# ProgrammerBoardV1.net
KiCad netlist of a schematic drawn in EAGLE
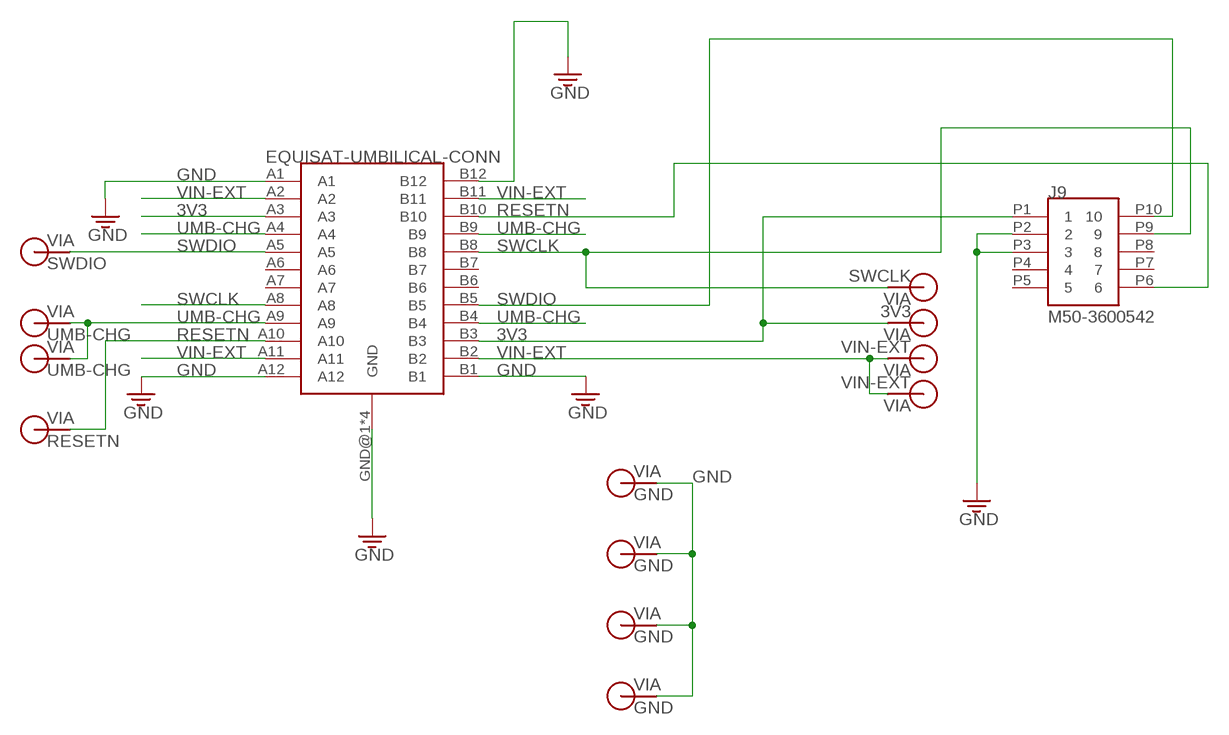
[diagram p0: schematic, sheet 1]

(export (version "E")
  (design (tool "Eeschema 10.0.6"))
  (components
    (comp (ref "J9")
      (value "M50-3600542")
      (footprint "eagle-import:10PINMALE")
      (libsource (lib "eagle-import") (part "10PINMALE"))
    )
    (comp (ref "U$1")
      (value "EQUISAT-UMBILICAL-CONN")
      (footprint "eagle-import:USB-C-RCPT-SMT")
      (libsource (lib "eagle-import") (part "EQUISAT-UMBILICAL-CONN"))
    )
    (comp (ref "V1")
      (value "GND")
      (footprint "eagle-import:VIA-60MIL")
      (libsource (lib "eagle-import") (part "VIA-60MIL"))
    )
    (comp (ref "V2")
      (value "GND")
      (footprint "eagle-import:VIA-60MIL")
      (libsource (lib "eagle-import") (part "VIA-60MIL"))
    )
    (comp (ref "V3")
      (value "GND")
      (footprint "eagle-import:VIA-60MIL")
      (libsource (lib "eagle-import") (part "VIA-60MIL"))
    )
    (comp (ref "V4")
      (value "GND")
      (footprint "eagle-import:VIA-60MIL")
      (libsource (lib "eagle-import") (part "VIA-60MIL"))
    )
    (comp (ref "V5")
      (value "SWDIO")
      (footprint "eagle-import:VIA-60MIL")
      (libsource (lib "eagle-import") (part "VIA-60MIL"))
    )
    (comp (ref "V6")
      (value "UMB-CHG")
      (footprint "eagle-import:VIA-60MIL")
      (libsource (lib "eagle-import") (part "VIA-60MIL"))
    )
    (comp (ref "V7")
      (value "UMB-CHG")
      (footprint "eagle-import:VIA-60MIL")
      (libsource (lib "eagle-import") (part "VIA-60MIL"))
    )
    (comp (ref "V8")
      (value "RESETN")
      (footprint "eagle-import:VIA-60MIL")
      (libsource (lib "eagle-import") (part "VIA-60MIL"))
    )
    (comp (ref "V9")
      (value "SWCLK")
      (footprint "eagle-import:VIA-60MIL")
      (libsource (lib "eagle-import") (part "VIA-60MIL"))
    )
    (comp (ref "V10")
      (value "3V3")
      (footprint "eagle-import:VIA-60MIL")
      (libsource (lib "eagle-import") (part "VIA-60MIL"))
    )
    (comp (ref "V11")
      (value "VIN-EXT")
      (footprint "eagle-import:VIA-60MIL")
      (libsource (lib "eagle-import") (part "VIA-60MIL"))
    )
    (comp (ref "V12")
      (value "VIN-EXT")
      (footprint "eagle-import:VIA-60MIL")
      (libsource (lib "eagle-import") (part "VIA-60MIL"))
    )
  )
  (nets
    (net (code "1") (name "/3V3") (class "Default")
      (node (ref "J9") (pin "P1") (pinfunction "1_P1") (pintype "bidirectional"))
      (node (ref "U$1") (pin "A3") (pinfunction "A3_A3") (pintype "bidirectional"))
      (node (ref "U$1") (pin "B3") (pinfunction "B3_B3") (pintype "bidirectional"))
      (node (ref "V10") (pin "P$1") (pinfunction "P$1_P$1") (pintype "bidirectional"))
    )
    (net (code "2") (name "/RESETN") (class "Default")
      (node (ref "J9") (pin "P6") (pinfunction "6_P6") (pintype "bidirectional"))
      (node (ref "U$1") (pin "A10") (pinfunction "A10_A10") (pintype "bidirectional"))
      (node (ref "U$1") (pin "B10") (pinfunction "B10_B10") (pintype "bidirectional"))
      (node (ref "V8") (pin "P$1") (pinfunction "P$1_P$1") (pintype "bidirectional"))
    )
    (net (code "3") (name "/SWCLK") (class "Default")
      (node (ref "J9") (pin "P9") (pinfunction "9_P9") (pintype "bidirectional"))
      (node (ref "U$1") (pin "A8") (pinfunction "A8_A8") (pintype "bidirectional"))
      (node (ref "U$1") (pin "B8") (pinfunction "B8_B8") (pintype "bidirectional"))
      (node (ref "V9") (pin "P$1") (pinfunction "P$1_P$1") (pintype "bidirectional"))
    )
    (net (code "4") (name "/SWDIO") (class "Default")
      (node (ref "J9") (pin "P10") (pinfunction "10_P10") (pintype "bidirectional"))
      (node (ref "U$1") (pin "A5") (pinfunction "A5_A5") (pintype "bidirectional"))
      (node (ref "U$1") (pin "B5") (pinfunction "B5_B5") (pintype "bidirectional"))
      (node (ref "V5") (pin "P$1") (pinfunction "P$1_P$1") (pintype "bidirectional"))
    )
    (net (code "5") (name "/UMB-CHG") (class "Default")
      (node (ref "U$1") (pin "A4") (pinfunction "A4_A4") (pintype "bidirectional"))
      (node (ref "U$1") (pin "A9") (pinfunction "A9_A9") (pintype "bidirectional"))
      (node (ref "U$1") (pin "B4") (pinfunction "B4_B4") (pintype "bidirectional"))
      (node (ref "U$1") (pin "B9") (pinfunction "B9_B9") (pintype "bidirectional"))
      (node (ref "V6") (pin "P$1") (pinfunction "P$1_P$1") (pintype "bidirectional"))
      (node (ref "V7") (pin "P$1") (pinfunction "P$1_P$1") (pintype "bidirectional"))
    )
    (net (code "6") (name "/VIN-EXT") (class "Default")
      (node (ref "U$1") (pin "A11") (pinfunction "A11_A11") (pintype "bidirectional"))
      (node (ref "U$1") (pin "A2") (pinfunction "A2_A2") (pintype "bidirectional"))
      (node (ref "U$1") (pin "B11") (pinfunction "B11_B11") (pintype "bidirectional"))
      (node (ref "U$1") (pin "B2") (pinfunction "B2_B2") (pintype "bidirectional"))
      (node (ref "V11") (pin "P$1") (pinfunction "P$1_P$1") (pintype "bidirectional"))
      (node (ref "V12") (pin "P$1") (pinfunction "P$1_P$1") (pintype "bidirectional"))
    )
    (net (code "7") (name "GND") (class "Default")
      (node (ref "J9") (pin "P2") (pinfunction "2_P2") (pintype "bidirectional"))
      (node (ref "J9") (pin "P3") (pinfunction "3_P3") (pintype "bidirectional"))
      (node (ref "U$1") (pin "A1") (pinfunction "A1_A1") (pintype "bidirectional"))
      (node (ref "U$1") (pin "A12") (pinfunction "A12_A12") (pintype "bidirectional"))
      (node (ref "U$1") (pin "B1") (pinfunction "B1_B1") (pintype "bidirectional"))
      (node (ref "U$1") (pin "B12") (pinfunction "B12_B12") (pintype "bidirectional"))
      (node (ref "U$1") (pin "GND@1") (pinfunction "GND_GND@1") (pintype "bidirectional"))
      (node (ref "U$1") (pin "GND@2") (pinfunction "GND_GND@2") (pintype "bidirectional"))
      (node (ref "U$1") (pin "GND@3") (pinfunction "GND_GND@3") (pintype "bidirectional"))
      (node (ref "U$1") (pin "GND@4") (pinfunction "GND_GND@4") (pintype "bidirectional"))
      (node (ref "V1") (pin "P$1") (pinfunction "P$1_P$1") (pintype "bidirectional"))
      (node (ref "V2") (pin "P$1") (pinfunction "P$1_P$1") (pintype "bidirectional"))
      (node (ref "V3") (pin "P$1") (pinfunction "P$1_P$1") (pintype "bidirectional"))
      (node (ref "V4") (pin "P$1") (pinfunction "P$1_P$1") (pintype "bidirectional"))
    )
    (net (code "8") (name "unconnected-(J9-4-PadP4)") (class "Default")
      (node (ref "J9") (pin "P4") (pinfunction "4_P4") (pintype "bidirectional"))
    )
    (net (code "9") (name "unconnected-(J9-5-PadP5)") (class "Default")
      (node (ref "J9") (pin "P5") (pinfunction "5_P5") (pintype "bidirectional"))
    )
    (net (code "10") (name "unconnected-(J9-7-PadP7)") (class "Default")
      (node (ref "J9") (pin "P7") (pinfunction "7_P7") (pintype "bidirectional"))
    )
    (net (code "11") (name "unconnected-(J9-8-PadP8)") (class "Default")
      (node (ref "J9") (pin "P8") (pinfunction "8_P8") (pintype "bidirectional"))
    )
    (net (code "12") (name "unconnected-(U$1-PadA6)") (class "Default")
      (node (ref "U$1") (pin "A6") (pinfunction "A6_A6") (pintype "bidirectional"))
    )
    (net (code "13") (name "unconnected-(U$1-PadA7)") (class "Default")
      (node (ref "U$1") (pin "A7") (pinfunction "A7_A7") (pintype "bidirectional"))
    )
    (net (code "14") (name "unconnected-(U$1-PadB6)") (class "Default")
      (node (ref "U$1") (pin "B6") (pinfunction "B6_B6") (pintype "bidirectional"))
    )
    (net (code "15") (name "unconnected-(U$1-PadB7)") (class "Default")
      (node (ref "U$1") (pin "B7") (pinfunction "B7_B7") (pintype "bidirectional"))
    )
  )
)
